# 411618_029_3_6.net
KiCad netlist of a schematic drawn in Altium Designer
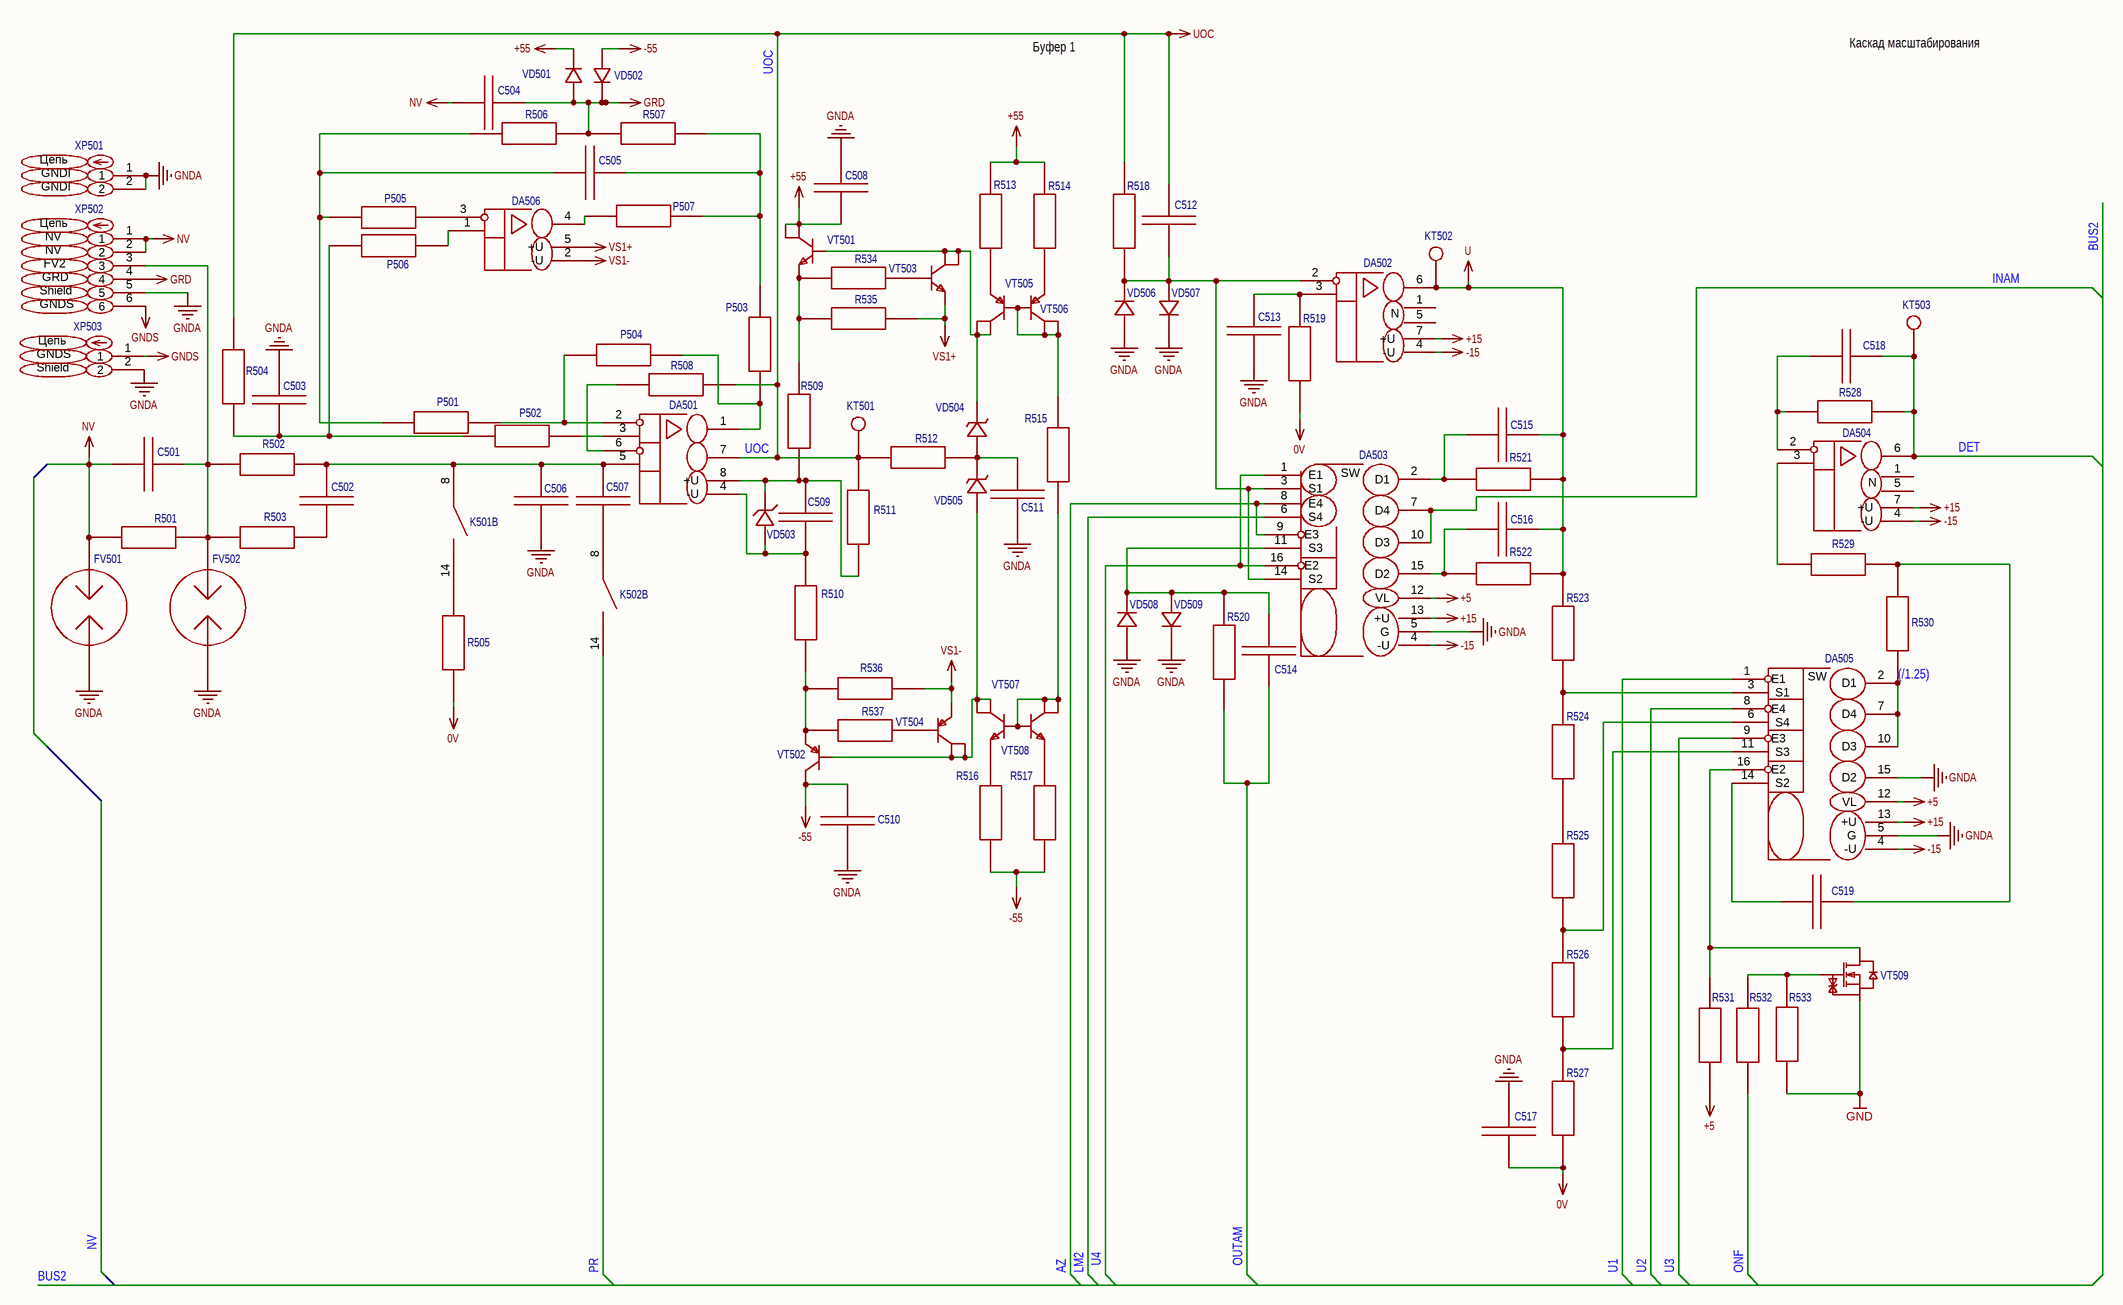
[diagram p0: УШЯИ.411618.029Э Э3 Лист 6.schdoc]

(export (version "E")
  (design (tool "Eeschema 10.0.6"))
  (components
    (comp (ref "C501")
      (value "Конденсатор К10-17Б М47 47пФ  NP0 5% [DIP]")
      (footprint "Конденсатор К10-17Б М47 X.X.xФ  NP0 5% [DIP 8мм]")
      (fields (field (name "MANUFACTURER PART") "К10-17Б М47") (field (name "CONTRIBUTOR") "jordanjin"))
      (libsource (lib "altium-import") (part "root_2_Конденсатор К10-17Б М47 47пФ  NP0 5% [DIP]_"))
    )
    (comp (ref "C502")
      (value "Конденсатор К10-17Б М47 47пФ  NP0 5% [DIP]")
      (footprint "Конденсатор К10-17Б М47 X.X.xФ  NP0 5% [DIP 8мм]")
      (fields (field (name "MANUFACTURER PART") "К10-17Б М47") (field (name "CONTRIBUTOR") "jordanjin"))
      (libsource (lib "altium-import") (part "root_3_Конденсатор К10-17Б М47 47пФ  NP0 5% [DIP]_"))
    )
    (comp (ref "C503")
      (value "Конденсатор SMD 10пФ 100В X7R 10% [0805]")
      (footprint "C0805")
      (fields (field (name "MANUFACTURER PART") "C0805") (field (name "CONTRIBUTOR") "jordanjin"))
      (libsource (lib "altium-import") (part "root_1_Конденсатор SMD 10пФ 100В X7R 10% [0805]_"))
    )
    (comp (ref "C504")
      (value "Конденсатор К10-17Б М47 0,022мкФ  NP0 5% [DIP]")
      (footprint "Конденсатор К10-17Б М47 X.X.xФ  NP0 5% [DIP 5мм]")
      (fields (field (name "MANUFACTURER PART") "К10-17Б М47") (field (name "CONTRIBUTOR") "jordanjin"))
      (libsource (lib "altium-import") (part "root_0_Конденсатор К10-17Б М47 0,022мкФ  NP0 5% [DIP]_"))
    )
    (comp (ref "C505")
      (value "Конденсатор SMD 10пФ 100В X7R 10% [0805]")
      (footprint "C0805")
      (fields (field (name "MANUFACTURER PART") "К10-17Б М47") (field (name "CONTRIBUTOR") "jordanjin"))
      (libsource (lib "altium-import") (part "root_0_Конденсатор К10-17Б М47 10пФ  NP0 5% [DIP]_"))
    )
    (comp (ref "C506")
      (value "Конденсатор К10-17Б М47 33пФ  NP0 5% [DIP]")
      (footprint "Конденсатор К10-17Б М47 X.X.xФ  NP0 5% [DIP 5мм]")
      (fields (field (name "MANUFACTURER PART") "К10-17Б М47") (field (name "CONTRIBUTOR") "jordanjin"))
      (libsource (lib "altium-import") (part "root_3_Конденсатор К10-17Б М47 33пФ  NP0 5% [DIP]_"))
    )
    (comp (ref "C507")
      (value "Конденсатор К10-17Б М47 47пФ  NP0 5% [DIP]")
      (footprint "Конденсатор К10-17Б М47 X.X.xФ  NP0 5% [DIP 5мм]")
      (fields (field (name "MANUFACTURER PART") "К10-17Б М47") (field (name "CONTRIBUTOR") "jordanjin"))
      (libsource (lib "altium-import") (part "root_1_Конденсатор К10-17Б М47 47пФ  NP0 5% [DIP]_"))
    )
    (comp (ref "C508")
      (value "Конденсатор SMD 0,068мкФ 100В X7R 10% [0805]")
      (footprint "C0805")
      (fields (field (name "MANUFACTURER PART") "C0805") (field (name "CONTRIBUTOR") "jordanjin"))
      (libsource (lib "altium-import") (part "root_1_Конденсатор SMD 0,068мкФ 100В X7R 10% [0805]_"))
    )
    (comp (ref "C509")
      (value "Конденсатор SMD 5600пФ 100В X7R 10% [0805]")
      (footprint "C0805")
      (fields (field (name "MANUFACTURER PART") "C0805") (field (name "CONTRIBUTOR") "jordanjin"))
      (libsource (lib "altium-import") (part "root_1_Конденсатор SMD 5600пФ 100В X7R 10% [0805]_"))
    )
    (comp (ref "C510")
      (value "Конденсатор SMD 0,068мкФ 100В X7R 10% [0805]")
      (footprint "C0805")
      (fields (field (name "MANUFACTURER PART") "C0805") (field (name "CONTRIBUTOR") "jordanjin"))
      (libsource (lib "altium-import") (part "root_3_Конденсатор SMD 0,068мкФ 100В X7R 10% [0805]_"))
    )
    (comp (ref "C511")
      (value "Конденсатор SMD 100пФ 100В X7R 10% [0805]")
      (footprint "C0805")
      (fields (field (name "MANUFACTURER PART") "C0805") (field (name "CONTRIBUTOR") "jordanjin"))
      (libsource (lib "altium-import") (part "root_1_Конденсатор SMD 100пФ 100В X7R 10% [0805]_"))
    )
    (comp (ref "C512")
      (value "Конденсатор SMD 10пФ 100В X7R 10% [0805]")
      (footprint "C0805")
      (fields (field (name "MANUFACTURER PART") "C0805") (field (name "CONTRIBUTOR") "jordanjin"))
      (libsource (lib "altium-import") (part "root_1_Конденсатор SMD 10пФ 100В X7R 10% [0805]_"))
    )
    (comp (ref "C513")
      (value "Конденсатор SMD 51пФ 100В X7R 10% [0805]")
      (footprint "C0805")
      (fields (field (name "MANUFACTURER PART") "C0805") (field (name "CONTRIBUTOR") "jordanjin"))
      (libsource (lib "altium-import") (part "root_3_Конденсатор SMD 51пФ 100В X7R 10% [0805]_"))
    )
    (comp (ref "C514")
      (value "Конденсатор SMD 1500пФ 100В X7R 10% [0805]")
      (footprint "C0805")
      (fields (field (name "MANUFACTURER PART") "C0805") (field (name "CONTRIBUTOR") "jordanjin"))
      (libsource (lib "altium-import") (part "root_1_Конденсатор SMD 1500пФ 100В X7R 10% [0805]_"))
    )
    (comp (ref "C515")
      (value "Конденсатор SMD 100пФ 100В X7R 10% [0805]")
      (footprint "C0805")
      (fields (field (name "MANUFACTURER PART") "C0805") (field (name "CONTRIBUTOR") "jordanjin"))
      (libsource (lib "altium-import") (part "root_2_Конденсатор SMD 100пФ 100В X7R 10% [0805]_"))
    )
    (comp (ref "C516")
      (value "Конденсатор SMD 10пФ 100В X7R 10% [0805]")
      (footprint "C0805")
      (fields (field (name "MANUFACTURER PART") "C0805") (field (name "CONTRIBUTOR") "jordanjin"))
      (libsource (lib "altium-import") (part "root_2_Конденсатор SMD 10пФ 100В X7R 10% [0805]_"))
    )
    (comp (ref "C517")
      (value "Конденсатор SMD 240пФ 100В X7R 10% [0805]")
      (footprint "C0805")
      (fields (field (name "MANUFACTURER PART") "C0805") (field (name "CONTRIBUTOR") "jordanjin"))
      (libsource (lib "altium-import") (part "root_3_Конденсатор SMD 240пФ 100В X7R 10% [0805]_"))
    )
    (comp (ref "C518")
      (value "Конденсатор SMD 33пФ 100В X7R 10% [0805]")
      (footprint "C0805")
      (fields (field (name "MANUFACTURER PART") "C0805") (field (name "CONTRIBUTOR") "jordanjin"))
      (libsource (lib "altium-import") (part "root_0_Конденсатор SMD 33пФ 100В X7R 10% [0805]_"))
    )
    (comp (ref "C519")
      (value "Конденсатор SMD 1500пФ 100В X7R 10% [0805]")
      (footprint "C0805")
      (fields (field (name "MANUFACTURER PART") "C0805") (field (name "CONTRIBUTOR") "jordanjin"))
      (libsource (lib "altium-import") (part "root_0_Конденсатор SMD 1500пФ 100В X7R 10% [0805]_"))
    )
    (comp (ref "DA501")
      (value "Операционный усилитель TLV9152IDR [SOIC-8]")
      (footprint "SOIC-8_L4.9-W3.9-P1.27-LS6.0-BL")
      (fields
        (field (name "SUBPART_NO") "1")
        (field (name "MANUFACTURER") "TI")
        (field (name "MANUFACTURER PART") "TLV9152IDR")
        (field (name "CONTRIBUTOR") "jordanjin")
      )
      (libsource (lib "altium-import") (part "root_0_Операционный усилитель TLV9152IDR [SOIC-8]_"))
    )
    (comp (ref "DA502")
      (value "Операционный усилитель ADA4627-1BRZ [SOIC-8]")
      (footprint "SOIC-8_L5.0-W4.0-P1.27-LS6.1-BL")
      (fields
        (field (name "MANUFACTURER") "Analog Devices")
        (field (name "MANUFACTURER PART") "ADA4627-1BRZ")
        (field (name "CONTRIBUTOR") "jordanjin")
      )
      (libsource (lib "altium-import") (part "root_0_Операционный усилитель ADA4627-1BRZ [SOIC-8]_"))
    )
    (comp (ref "DA503")
      (value "Коммутатор аналоговых сигналов ADG433BRZ [SOIC-16]")
      (footprint "SOIC-16_L9.9-W3.9-P1.27-LS6.0-BL")
      (fields
        (field (name "MANUFACTURER") "Analog Devices")
        (field (name "MANUFACTURER PART") "ADG433BRZ-REEL")
        (field (name "CONTRIBUTOR") "jordanjin")
      )
      (libsource (lib "altium-import") (part "root_0_Коммутатор аналоговых сигналов ADG433BRZ [SOIC-16]_"))
    )
    (comp (ref "DA504")
      (value "Операционный усилитель ADA4627-1BRZ [SOIC-8]")
      (footprint "SOIC-8_L5.0-W4.0-P1.27-LS6.1-BL")
      (fields
        (field (name "MANUFACTURER") "Analog Devices")
        (field (name "MANUFACTURER PART") "ADA4627-1BRZ")
        (field (name "CONTRIBUTOR") "jordanjin")
      )
      (libsource (lib "altium-import") (part "root_0_Операционный усилитель ADA4627-1BRZ [SOIC-8]_"))
    )
    (comp (ref "DA505")
      (value "Коммутатор аналоговых сигналов ADG431BRZ [SOIC-16]")
      (footprint "SOIC-16_L9.9-W3.9-P1.27-LS6.0-BL")
      (fields
        (field (name "MANUFACTURER") "Analog Devices")
        (field (name "MANUFACTURER PART") "ADG431BRZ")
        (field (name "CONTRIBUTOR") "jordanjin")
      )
      (libsource (lib "altium-import") (part "root_0_Коммутатор аналоговых сигналов ADG431BRZ [SOIC-16]_"))
    )
    (comp (ref "DA506")
      (value "Операционный усилитель  TLV9151IDCKR [SC-70-5]")
      (footprint "SC-70-5_L2.1-W1.3-P0.65-LS2.2-BR")
      (fields
        (field (name "MANUFACTURER") "TI")
        (field (name "MANUFACTURER PART") "TLV9151IDCKR")
        (field (name "CONTRIBUTOR") "jordanjin")
      )
      (libsource (lib "altium-import") (part "root_0_Операционный усилитель  TLV9151IDCKR [SC-70-5]_"))
    )
    (comp (ref "FV501")
      (value "Разрядник газонаполненный B88069-X8870-B502 (A81-C90X)")
      (fields
        (field (name "MANUFACTURER") "TDK/EPCOS")
        (field (name "MANUFACTURER PART") "B88069-X8870-B502 (A81-C90X)")
        (field (name "CONTRIBUTOR") "jordanjin")
      )
      (libsource (lib "altium-import") (part "root_0_Разрядник газонаполненный B88069-X8870-B502 (A81-C90X)_"))
    )
    (comp (ref "FV502")
      (value "Разрядник газонаполненный B88069-X8870-B502 (A81-C90X)")
      (fields
        (field (name "MANUFACTURER") "TDK/EPCOS")
        (field (name "MANUFACTURER PART") "B88069-X8870-B502 (A81-C90X)")
        (field (name "CONTRIBUTOR") "jordanjin")
      )
      (libsource (lib "altium-import") (part "root_0_Разрядник газонаполненный B88069-X8870-B502 (A81-C90X)_"))
    )
    (comp (ref "K501")
      (value "Реле герконовое DIP05-1A72-13L  [PCB]")
      (footprint "RELAY-TH_STANDEXMEDER_DIP05-1A72-13L")
      (fields
        (field (name "MANUFACTURER") "STANDEXMEDER")
        (field (name "MANUFACTURER PART") "DIP05-1A72-13L")
        (field (name "SUBPART_NO") "2")
        (field (name "CONTRIBUTOR") "jordanjin")
      )
      (libsource (lib "altium-import") (part "root_0_Реле герконовое DIP05-1A72-13L  [PCB]_"))
    )
    (comp (ref "K502")
      (value "Реле герконовое DIP05-1A72-13L  [PCB]")
      (footprint "RELAY-TH_STANDEXMEDER_DIP05-1A72-13L")
      (fields
        (field (name "MANUFACTURER") "STANDEXMEDER")
        (field (name "MANUFACTURER PART") "DIP05-1A72-13L")
        (field (name "SUBPART_NO") "2")
        (field (name "CONTRIBUTOR") "jordanjin")
      )
      (libsource (lib "altium-import") (part "root_0_Реле герконовое DIP05-1A72-13L  [PCB]_"))
    )
    (comp (ref "KT501")
      (value "Control point")
      (fields (field (name "CONTRIBUTOR") "jordanjin"))
      (libsource (lib "altium-import") (part "root_2_Control point_"))
    )
    (comp (ref "KT502")
      (value "Control point")
      (fields (field (name "CONTRIBUTOR") "jordanjin"))
      (libsource (lib "altium-import") (part "root_2_Control point_"))
    )
    (comp (ref "KT503")
      (value "Control point")
      (fields (field (name "CONTRIBUTOR") "jordanjin"))
      (libsource (lib "altium-import") (part "root_2_Control point_"))
    )
    (comp (ref "P501")
      (value "Перемычка")
      (footprint "R0805")
      (fields (field (name "MANUFACTURER PART") "R0805") (field (name "CONTRIBUTOR") "jordanjin"))
      (libsource (lib "altium-import") (part "root_2_Перемычка_"))
    )
    (comp (ref "P502")
      (value "Перемычка")
      (footprint "R0805")
      (fields (field (name "MANUFACTURER PART") "R0805") (field (name "CONTRIBUTOR") "jordanjin"))
      (libsource (lib "altium-import") (part "root_2_Перемычка_"))
    )
    (comp (ref "P503")
      (value "Перемычка")
      (footprint "R0805")
      (fields (field (name "MANUFACTURER PART") "R0805") (field (name "CONTRIBUTOR") "jordanjin"))
      (libsource (lib "altium-import") (part "root_1_Перемычка_"))
    )
    (comp (ref "P504")
      (value "Перемычка")
      (footprint "R0805")
      (fields (field (name "MANUFACTURER PART") "R0805") (field (name "CONTRIBUTOR") "jordanjin"))
      (libsource (lib "altium-import") (part "root_2_Перемычка_"))
    )
    (comp (ref "P505")
      (value "Перемычка")
      (footprint "R0805")
      (fields (field (name "MANUFACTURER PART") "R0805") (field (name "CONTRIBUTOR") "jordanjin"))
      (libsource (lib "altium-import") (part "root_2_Перемычка_"))
    )
    (comp (ref "P506")
      (value "Перемычка")
      (footprint "R0805")
      (fields (field (name "MANUFACTURER PART") "R0805") (field (name "CONTRIBUTOR") "jordanjin"))
      (libsource (lib "altium-import") (part "root_2_Перемычка_"))
    )
    (comp (ref "P507")
      (value "Перемычка")
      (footprint "R0805")
      (fields (field (name "MANUFACTURER PART") "R0805") (field (name "CONTRIBUTOR") "jordanjin"))
      (libsource (lib "altium-import") (part "root_2_Перемычка_"))
    )
    (comp (ref "R501")
      (value "Резистор C2-29В-0,25 1,2кОм ±0,5% [DIP]")
      (fields (field (name "MANUFACTURER PART") "C2-29В-0,25") (field (name "CONTRIBUTOR") "jordanjin"))
      (libsource (lib "altium-import") (part "root_0_Резистор C2-29В-0,25 1,2кОм ±0,5% [DIP]_"))
    )
    (comp (ref "R502")
      (value "Резистор C2-29В-0,25 301кОм ±0,5% [DIP]")
      (fields (field (name "MANUFACTURER PART") "C2-29В-0,25") (field (name "CONTRIBUTOR") "jordanjin"))
      (libsource (lib "altium-import") (part "root_0_Резистор C2-29В-0,25 301кОм ±0,5% [DIP]_"))
    )
    (comp (ref "R503")
      (value "Резистор C2-29В-0,25 5.1кОм ±0,5% [DIP]")
      (fields (field (name "MANUFACTURER PART") "C2-29В-0,25") (field (name "CONTRIBUTOR") "jordanjin"))
      (libsource (lib "altium-import") (part "root_0_Резистор C2-29В-0,25 5.1кОм ±0,5% [DIP]_"))
    )
    (comp (ref "R504")
      (value "Резистор 91кОм 0,125Вт 1% [0805]")
      (footprint "R0805")
      (fields (field (name "MANUFACTURER PART") "R0805") (field (name "CONTRIBUTOR") "jordanjin"))
      (libsource (lib "altium-import") (part "root_1_Резистор 91кОм 0,125Вт 1% [0805]_"))
    )
    (comp (ref "R505")
      (value "Резистор 2.4кОм 0,25Вт 1% [1206]")
      (footprint "R1206")
      (fields (field (name "MANUFACTURER PART") "C2-29В-0,25") (field (name "CONTRIBUTOR") "jordanjin"))
      (libsource (lib "altium-import") (part "root_1_Резистор C2-29В-0,25 2.4кОм ±0,5% [DIP]_"))
    )
    (comp (ref "R506")
      (value "Резистор C2-29В-0,25 51Ом ±0,5% [DIP]")
      (fields (field (name "MANUFACTURER PART") "C2-29В-0,25") (field (name "CONTRIBUTOR") "jordanjin"))
      (libsource (lib "altium-import") (part "root_0_Резистор C2-29В-0,25 51Ом ±0,5% [DIP]_"))
    )
    (comp (ref "R507")
      (value "Резистор C2-29В-0,25 22Ом ±0,5% [DIP]")
      (fields (field (name "MANUFACTURER PART") "C2-29В-0,25") (field (name "CONTRIBUTOR") "jordanjin"))
      (libsource (lib "altium-import") (part "root_0_Резистор C2-29В-0,25 22Ом ±0,5% [DIP]_"))
    )
    (comp (ref "R508")
      (value "Резистор 33Ом 0,125Вт 1% [0805]")
      (footprint "R0805")
      (fields (field (name "MANUFACTURER PART") "R0805") (field (name "CONTRIBUTOR") "jordanjin"))
      (libsource (lib "altium-import") (part "root_0_Резистор 33Ом 0,125Вт 1% [0805]_"))
    )
    (comp (ref "R509")
      (value "Резистор 150Ом 0,125Вт 1% [0805]")
      (footprint "R0805")
      (fields (field (name "MANUFACTURER PART") "R0805") (field (name "CONTRIBUTOR") "jordanjin"))
      (libsource (lib "altium-import") (part "root_1_Резистор 150Ом 0,125Вт 1% [0805]_"))
    )
    (comp (ref "R510")
      (value "Резистор 150Ом 0,125Вт 1% [0805]")
      (footprint "R0805")
      (fields (field (name "MANUFACTURER PART") "R0805") (field (name "CONTRIBUTOR") "jordanjin"))
      (libsource (lib "altium-import") (part "root_1_Резистор 150Ом 0,125Вт 1% [0805]_"))
    )
    (comp (ref "R511")
      (value "Резистор 5,1кОм 0,125Вт 1% [0805]")
      (footprint "R0805")
      (fields (field (name "MANUFACTURER PART") "R0805") (field (name "CONTRIBUTOR") "jordanjin"))
      (libsource (lib "altium-import") (part "root_3_Резистор 5,1кОм 0,125Вт 1% [0805]_"))
    )
    (comp (ref "R512")
      (value "Резистор 4,7кОм 0,125Вт 1% [0805]")
      (footprint "R0805")
      (fields (field (name "MANUFACTURER PART") "R0805") (field (name "CONTRIBUTOR") "jordanjin"))
      (libsource (lib "altium-import") (part "root_0_Резистор 4,7кОм 0,125Вт 1% [0805]_"))
    )
    (comp (ref "R513")
      (value "Резистор 820Ом 0,125Вт 1% [0805]")
      (footprint "R0805")
      (fields (field (name "MANUFACTURER PART") "R0805") (field (name "CONTRIBUTOR") "jordanjin"))
      (libsource (lib "altium-import") (part "root_1_Резистор 820Ом 0,125Вт 1% [0805]_"))
    )
    (comp (ref "R514")
      (value "Резистор 2кОм 0,125Вт 1% [0805]")
      (footprint "R0805")
      (fields (field (name "MANUFACTURER PART") "R0805") (field (name "CONTRIBUTOR") "jordanjin"))
      (libsource (lib "altium-import") (part "root_1_Резистор 2кОм 0,125Вт 1% [0805]_"))
    )
    (comp (ref "R515")
      (value "Резистор 200кОм 0,125Вт 1% [0805]")
      (footprint "R0805")
      (fields (field (name "MANUFACTURER PART") "R0805") (field (name "CONTRIBUTOR") "jordanjin"))
      (libsource (lib "altium-import") (part "root_1_Резистор 200кОм 0,125Вт 1% [0805]_"))
    )
    (comp (ref "R516")
      (value "Резистор 820Ом 0,125Вт 1% [0805]")
      (footprint "R0805")
      (fields (field (name "MANUFACTURER PART") "R0805") (field (name "CONTRIBUTOR") "jordanjin"))
      (libsource (lib "altium-import") (part "root_1_Резистор 820Ом 0,125Вт 1% [0805]_"))
    )
    (comp (ref "R517")
      (value "Резистор 2кОм 0,125Вт 1% [0805]")
      (footprint "R0805")
      (fields (field (name "MANUFACTURER PART") "R0805") (field (name "CONTRIBUTOR") "jordanjin"))
      (libsource (lib "altium-import") (part "root_1_Резистор 2кОм 0,125Вт 1% [0805]_"))
    )
    (comp (ref "R518")
      (value "Резистор 40,2кОм 0.25Вт 1% [1206]")
      (footprint "R0805")
      (fields (field (name "MANUFACTURER PART") "R0805") (field (name "CONTRIBUTOR") "jordanjin"))
      (libsource (lib "altium-import") (part "root_3_Резистор 40,2кОм 0.25Вт 1% [1206]_"))
    )
    (comp (ref "R519")
      (value "Резистор 15кОм 0,125Вт 1% [0805]")
      (footprint "R0805")
      (fields (field (name "MANUFACTURER PART") "R0805") (field (name "CONTRIBUTOR") "jordanjin"))
      (libsource (lib "altium-import") (part "root_1_Резистор 15кОм 0,125Вт 1% [0805]_"))
    )
    (comp (ref "R520")
      (value "Резистор 200кОм 0,125Вт 1% [0805]")
      (footprint "R0805")
      (fields (field (name "MANUFACTURER PART") "R0805") (field (name "CONTRIBUTOR") "jordanjin"))
      (libsource (lib "altium-import") (part "root_3_Резистор 200кОм 0,125Вт 1% [0805]_"))
    )
    (comp (ref "R521")
      (value "Резистор 10кОм 0,125Вт 1% [0805]")
      (footprint "R0805")
      (fields (field (name "MANUFACTURER PART") "R0805") (field (name "CONTRIBUTOR") "jordanjin"))
      (libsource (lib "altium-import") (part "root_0_Резистор 10кОм 0,125Вт 1% [0805]_"))
    )
    (comp (ref "R522")
      (value "Резистор 100кОм 0,125Вт 1% [0805]")
      (footprint "R0805")
      (fields (field (name "MANUFACTURER PART") "R0805") (field (name "CONTRIBUTOR") "jordanjin"))
      (libsource (lib "altium-import") (part "root_0_Резистор 100кОм 0,125Вт 1% [0805]_"))
    )
    (comp (ref "R523")
      (value "Резистор 4,02кОм 0.25Вт 1% [1206]")
      (footprint "R1206")
      (fields (field (name "MANUFACTURER PART") "R1206") (field (name "CONTRIBUTOR") "jordanjin"))
      (libsource (lib "altium-import") (part "root_1_Резистор 4,02кОм 0.25Вт 1% [1206]_"))
    )
    (comp (ref "R524")
      (value "Резистор 4,02кОм 0.25Вт 1% [1206]")
      (footprint "R1206")
      (fields (field (name "MANUFACTURER PART") "R1206") (field (name "CONTRIBUTOR") "jordanjin"))
      (libsource (lib "altium-import") (part "root_1_Резистор 4,02кОм 0.25Вт 1% [1206]_"))
    )
    (comp (ref "R525")
      (value "Резистор 4,02кОм 0.25Вт 1% [1206]")
      (footprint "R1206")
      (fields (field (name "MANUFACTURER PART") "R1206") (field (name "CONTRIBUTOR") "jordanjin"))
      (libsource (lib "altium-import") (part "root_1_Резистор 4,02кОм 0.25Вт 1% [1206]_"))
    )
    (comp (ref "R526")
      (value "Резистор 4,02кОм 0.25Вт 1% [1206]")
      (footprint "R1206")
      (fields (field (name "MANUFACTURER PART") "R1206") (field (name "CONTRIBUTOR") "jordanjin"))
      (libsource (lib "altium-import") (part "root_1_Резистор 4,02кОм 0.25Вт 1% [1206]_"))
    )
    (comp (ref "R527")
      (value "Резистор 4,02кОм 0.25Вт 1% [1206]")
      (footprint "R1206")
      (fields (field (name "MANUFACTURER PART") "R1206") (field (name "CONTRIBUTOR") "jordanjin"))
      (libsource (lib "altium-import") (part "root_1_Резистор 4,02кОм 0.25Вт 1% [1206]_"))
    )
    (comp (ref "R528")
      (value "Резистор 3,6кОм 0,125Вт 1% [0805]")
      (footprint "R0805")
      (fields (field (name "MANUFACTURER PART") "R0805") (field (name "CONTRIBUTOR") "jordanjin"))
      (libsource (lib "altium-import") (part "root_2_Резистор 3,6кОм 0,125Вт 1% [0805]_"))
    )
    (comp (ref "R529")
      (value "Резистор 110кОм 0,125Вт 1% [0805]")
      (footprint "R0805")
      (fields (field (name "MANUFACTURER PART") "R0805") (field (name "CONTRIBUTOR") "jordanjin"))
      (libsource (lib "altium-import") (part "root_2_Резистор 110кОм 0,125Вт 1% [0805]_"))
    )
    (comp (ref "R530")
      (value "Резистор 110кОм 0,125Вт 1% [0805]")
      (footprint "R0805")
      (fields (field (name "MANUFACTURER PART") "R0805") (field (name "CONTRIBUTOR") "jordanjin"))
      (libsource (lib "altium-import") (part "root_1_Резистор 110кОм 0,125Вт 1% [0805]_"))
    )
    (comp (ref "R531")
      (value "Резистор 5,3кОм 0,125Вт 1% [0805]")
      (footprint "R0805")
      (fields (field (name "MANUFACTURER PART") "R0805") (field (name "CONTRIBUTOR") "jordanjin"))
      (libsource (lib "altium-import") (part "root_1_Резистор 5,3кОм 0,125Вт 1% [0805]_"))
    )
    (comp (ref "R532")
      (value "Резистор 100Ом 0,125Вт 1% [0805]")
      (footprint "R0805")
      (fields (field (name "MANUFACTURER PART") "R0805") (field (name "CONTRIBUTOR") "jordanjin"))
      (libsource (lib "altium-import") (part "root_1_Резистор 100Ом 0,125Вт 1% [0805]_"))
    )
    (comp (ref "R533")
      (value "Резистор 100Ом 0,125Вт 1% [0805]")
      (footprint "R0805")
      (fields (field (name "MANUFACTURER PART") "R0805") (field (name "CONTRIBUTOR") "jordanjin"))
      (libsource (lib "altium-import") (part "root_1_Резистор 100Ом 0,125Вт 1% [0805]_"))
    )
    (comp (ref "R534")
      (value "Резистор 400Ом 0,125Вт 1% [0805]")
      (footprint "R0805")
      (fields (field (name "MANUFACTURER PART") "R0805") (field (name "CONTRIBUTOR") "jordanjin"))
      (libsource (lib "altium-import") (part "root_2_Резистор 400Ом 0,125Вт 1% [0805]_"))
    )
    (comp (ref "R535")
      (value "Резистор 150Ом 0,125Вт 1% [0805]")
      (footprint "R0805")
      (fields (field (name "MANUFACTURER PART") "R0805") (field (name "CONTRIBUTOR") "jordanjin"))
      (libsource (lib "altium-import") (part "root_2_Резистор 150Ом 0,125Вт 1% [0805]_"))
    )
    (comp (ref "R536")
      (value "Резистор 150Ом 0,125Вт 1% [0805]")
      (footprint "R0805")
      (fields (field (name "MANUFACTURER PART") "R0805") (field (name "CONTRIBUTOR") "jordanjin"))
      (libsource (lib "altium-import") (part "root_2_Резистор 150Ом 0,125Вт 1% [0805]_"))
    )
    (comp (ref "R537")
      (value "Резистор 400Ом 0,125Вт 1% [0805]")
      (footprint "R0805")
      (fields (field (name "MANUFACTURER PART") "R0805") (field (name "CONTRIBUTOR") "jordanjin"))
      (libsource (lib "altium-import") (part "root_2_Резистор 400Ом 0,125Вт 1% [0805]_"))
    )
    (comp (ref "VD501")
      (value "Диод импульсный 1N4448 [DO-35]")
      (footprint "DO-35_BD2.0-L4.2-P8.20-D0.5-RD")
      (fields
        (field (name "MANUFACTURER") "onsemi")
        (field (name "MANUFACTURER PART") "1N4448TR")
        (field (name "CONTRIBUTOR") "jordanjin")
      )
      (libsource (lib "altium-import") (part "root_3_Диод импульсный 1N4448 [DO-35]_"))
    )
    (comp (ref "VD502")
      (value "Диод импульсный 1N4448 [DO-35]")
      (footprint "DO-35_BD2.0-L4.2-P8.20-D0.5-RD")
      (fields
        (field (name "MANUFACTURER") "onsemi")
        (field (name "MANUFACTURER PART") "1N4448TR")
        (field (name "CONTRIBUTOR") "jordanjin")
      )
      (libsource (lib "altium-import") (part "root_1_Диод импульсный 1N4448 [DO-35]_"))
    )
    (comp (ref "VD503")
      (value "Стабилитрон MMSZ5230B 4.7В 0.5Вт [SOD123]")
      (footprint "SOD-123_L2.8-W1.8-LS3.7-RD")
      (fields (field (name "MANUFACTURER PART") "MMSZ5230B") (field (name "MANUFACTURER") "CJ(江苏长电/长晶)"))
      (libsource (lib "altium-import") (part "root_3_Стабилитрон MMSZ5230B 4.7В 0.5Вт [SOD123]_"))
    )
    (comp (ref "VD504")
      (value "Стабилитрон MMSZ5232B 5.6В 0.5Вт [SOD123]")
      (footprint "SOD-123_L2.7-W1.6-LS3.7-RD")
      (fields
        (field (name "MANUFACTURER") "MCC(美微科)")
        (field (name "MANUFACTURER PART") "MMSZ5232B-TP")
        (field (name "CONTRIBUTOR") "LCSC")
      )
      (libsource (lib "altium-import") (part "root_3_Стабилитрон MMSZ5232B 5.6В 0.5Вт [SOD123]_"))
    )
    (comp (ref "VD505")
      (value "Стабилитрон MMSZ5232B 5.6В 0.5Вт [SOD123]")
      (footprint "SOD-123_L2.7-W1.6-LS3.7-RD")
      (fields
        (field (name "MANUFACTURER") "MCC(美微科)")
        (field (name "MANUFACTURER PART") "MMSZ5232B-TP")
        (field (name "CONTRIBUTOR") "LCSC")
      )
      (libsource (lib "altium-import") (part "root_3_Стабилитрон MMSZ5232B 5.6В 0.5Вт [SOD123]_"))
    )
    (comp (ref "VD506")
      (value "Диод импульсный 1N4448 [SOD-123]")
      (footprint "SOD-123_L2.7-W1.6-LS3.7-RD-1")
      (fields
        (field (name "MANUFACTURER") "YANGJIE")
        (field (name "MANUFACTURER PART") "1N4448WQ")
        (field (name "CONTRIBUTOR") "jordanjin")
      )
      (libsource (lib "altium-import") (part "root_3_Диод импульсный 1N4448 [SOD-123]_"))
    )
    (comp (ref "VD507")
      (value "Диод импульсный 1N4448 [SOD-123]")
      (footprint "SOD-123_L2.7-W1.6-LS3.7-RD-1")
      (fields
        (field (name "MANUFACTURER") "YANGJIE")
        (field (name "MANUFACTURER PART") "1N4448WQ")
        (field (name "CONTRIBUTOR") "jordanjin")
      )
      (libsource (lib "altium-import") (part "root_1_Диод импульсный 1N4448 [SOD-123]_"))
    )
    (comp (ref "VD508")
      (value "Диод импульсный 1N4448 [SOD-123]")
      (footprint "SOD-123_L2.7-W1.6-LS3.7-RD-1")
      (fields
        (field (name "MANUFACTURER") "YANGJIE")
        (field (name "MANUFACTURER PART") "1N4448WQ")
        (field (name "CONTRIBUTOR") "jordanjin")
      )
      (libsource (lib "altium-import") (part "root_3_Диод импульсный 1N4448 [SOD-123]_"))
    )
    (comp (ref "VD509")
      (value "Диод импульсный 1N4448 [SOD-123]")
      (footprint "SOD-123_L2.7-W1.6-LS3.7-RD-1")
      (fields
        (field (name "MANUFACTURER") "YANGJIE")
        (field (name "MANUFACTURER PART") "1N4448WQ")
        (field (name "CONTRIBUTOR") "jordanjin")
      )
      (libsource (lib "altium-import") (part "root_1_Диод импульсный 1N4448 [SOD-123]_"))
    )
    (comp (ref "VT501")
      (value "Транзистор DZT658 NPN [SOT223]")
      (footprint "SOT-223-3_L6.5-W3.4-P2.30-LS7.0-BR")
      (fields
        (field (name "MANUFACTURER") "DIODES(美台)")
        (field (name "MANUFACTURER PART") "DZT658-13")
        (field (name "CONTRIBUTOR") "LCSC")
      )
      (libsource (lib "altium-import") (part "root_0_Транзистор DZT658 NPN [SOT223]_"))
    )
    (comp (ref "VT502")
      (value "Транзистор FZT758 PNP [SOT223]")
      (footprint "SOT-223_L6.5-W3.5-P2.30-LS7.0-BR")
      (fields
        (field (name "MANUFACTURER") "DIODES(美台)")
        (field (name "MANUFACTURER PART") "FZT758TA")
        (field (name "CONTRIBUTOR") "LCSC")
      )
      (libsource (lib "altium-import") (part "root_0_Транзистор FZT758 PNP [SOT223]_"))
    )
    (comp (ref "VT503")
      (value "Транзистор DZTA42 NPN [SOT223]")
      (footprint "SOT-223-4_L6.5-W3.5-P2.30-LS7.0-BR")
      (fields
        (field (name "MANUFACTURER") "DIODES(美台)")
        (field (name "MANUFACTURER PART") "DZTA42-13")
        (field (name "CONTRIBUTOR") "LCSC")
      )
      (libsource (lib "altium-import") (part "root_0_Транзистор DZTA42 NPN [SOT223]_"))
    )
    (comp (ref "VT504")
      (value "Транзистор DZTA92 PNP [SOT223]")
      (footprint "SOT-223-3_L6.5-W3.4-P2.30-LS7.0-BR")
      (fields
        (field (name "MANUFACTURER") "DIODES(美台)")
        (field (name "MANUFACTURER PART") "DZTA92-13")
        (field (name "CONTRIBUTOR") "lcsc")
      )
      (libsource (lib "altium-import") (part "root_0_Транзистор DZTA92 PNP [SOT223]_"))
    )
    (comp (ref "VT505")
      (value "Транзистор DZTA92 PNP [SOT223]")
      (footprint "SOT-223-3_L6.5-W3.4-P2.30-LS7.0-BR")
      (fields
        (field (name "MANUFACTURER") "DIODES(美台)")
        (field (name "MANUFACTURER PART") "DZTA92-13")
        (field (name "CONTRIBUTOR") "lcsc")
      )
      (libsource (lib "") (part "root_0_Транзистор DZTA92 PNP [SOT223]__1"))
    )
    (comp (ref "VT506")
      (value "Транзистор DZTA92 PNP [SOT223]")
      (footprint "SOT-223-3_L6.5-W3.4-P2.30-LS7.0-BR")
      (fields
        (field (name "MANUFACTURER") "DIODES(美台)")
        (field (name "MANUFACTURER PART") "DZTA92-13")
        (field (name "CONTRIBUTOR") "lcsc")
      )
      (libsource (lib "altium-import") (part "root_0_Транзистор DZTA92 PNP [SOT223]_"))
    )
    (comp (ref "VT507")
      (value "Транзистор DZTA42 NPN [SOT223]")
      (footprint "SOT-223-4_L6.5-W3.5-P2.30-LS7.0-BR")
      (fields
        (field (name "MANUFACTURER") "DIODES(美台)")
        (field (name "MANUFACTURER PART") "DZTA42-13")
        (field (name "CONTRIBUTOR") "LCSC")
      )
      (libsource (lib "") (part "root_0_Транзистор DZTA42 NPN [SOT223]__1"))
    )
    (comp (ref "VT508")
      (value "Транзистор DZTA42 NPN [SOT223]")
      (footprint "SOT-223-4_L6.5-W3.5-P2.30-LS7.0-BR")
      (fields
        (field (name "MANUFACTURER") "DIODES(美台)")
        (field (name "MANUFACTURER PART") "DZTA42-13")
        (field (name "CONTRIBUTOR") "LCSC")
      )
      (libsource (lib "altium-import") (part "root_0_Транзистор DZTA42 NPN [SOT223]_"))
    )
    (comp (ref "VT509")
      (value "Транзистор полевой MOSFET N-канальный BSS138BK [SOT-23-3]")
      (footprint "SOT-23-3_L2.9-W1.3-P1.90-LS2.4-BR")
      (fields
        (field (name "MANUFACTURER") "ElecSuper(静芯)")
        (field (name "MANUFACTURER PART") "BSS138BK")
        (field (name "CONTRIBUTOR") "lcsc")
      )
      (libsource (lib "altium-import") (part "root_0_Транзистор полевой MOSFET N-канальный BSS138BK [SOT-23-3]_"))
    )
    (comp (ref "XP501")
      (value "Вилка на плату 280370-2 шаг 2.54мм")
      (footprint "CONN-TH_280370-2")
      (fields
        (field (name "MANUFACTURER") "TE Connectivity")
        (field (name "MANUFACTURER PART") "280370-2")
        (field (name "CONTRIBUTOR") "jordanjin")
      )
      (libsource (lib "altium-import") (part "root_0_Вилка на плату 280370-2 шаг 2.54мм_"))
    )
    (comp (ref "XP502")
      (value "Вилка на плату 280372-1 шаг 2.54мм")
      (footprint "CONN-TH_280372-1")
      (fields
        (field (name "MANUFACTURER") "TE Connectivity")
        (field (name "MANUFACTURER PART") "280372-1")
        (field (name "CONTRIBUTOR") "jordanjin")
      )
      (libsource (lib "altium-import") (part "root_0_Вилка на плату 280372-1 шаг 2.54мм_"))
    )
    (comp (ref "XP503")
      (value "Вилка на плату 280370-2 шаг 2.54мм")
      (footprint "CONN-TH_280370-2")
      (fields
        (field (name "MANUFACTURER") "TE Connectivity")
        (field (name "MANUFACTURER PART") "280370-2")
        (field (name "CONTRIBUTOR") "jordanjin")
      )
      (libsource (lib "altium-import") (part "root_0_Вилка на плату 280370-2 шаг 2.54мм_"))
    )
  )
  (nets
    (net (code "2") (name "+5") (class "Default")
      (node (ref "DA503") (pin "12") (pinfunction "VL_12") (pintype "passive"))
      (node (ref "DA505") (pin "12") (pinfunction "VL_12") (pintype "passive"))
      (node (ref "R531") (pin "1") (pinfunction "1_1") (pintype "passive"))
    )
    (net (code "3") (name "+15") (class "Default")
      (node (ref "DA502") (pin "7") (pinfunction "+U_7") (pintype "passive"))
      (node (ref "DA503") (pin "13") (pinfunction "+U_13") (pintype "passive"))
      (node (ref "DA504") (pin "7") (pinfunction "+U_7") (pintype "passive"))
      (node (ref "DA505") (pin "13") (pinfunction "+U_13") (pintype "passive"))
    )
    (net (code "4") (name "+55") (class "Default")
      (node (ref "C508") (pin "1") (pinfunction "1_1") (pintype "passive"))
      (node (ref "R513") (pin "2") (pinfunction "2_2") (pintype "passive"))
      (node (ref "R514") (pin "2") (pinfunction "2_2") (pintype "passive"))
      (node (ref "VD501") (pin "1") (pinfunction "1_1") (pintype "passive"))
      (node (ref "VT501") (pin "2") (pinfunction "C_2") (pintype "passive"))
      (node (ref "VT501") (pin "4") (pinfunction "C_4") (pintype "passive"))
    )
    (net (code "5") (name "-15") (class "Default")
      (node (ref "DA502") (pin "4") (pinfunction "-U_4") (pintype "passive"))
      (node (ref "DA503") (pin "4") (pinfunction "-U_4") (pintype "passive"))
      (node (ref "DA504") (pin "4") (pinfunction "-U_4") (pintype "passive"))
      (node (ref "DA505") (pin "4") (pinfunction "-U_4") (pintype "passive"))
    )
    (net (code "6") (name "-55") (class "Default")
      (node (ref "C510") (pin "1") (pinfunction "1_1") (pintype "passive"))
      (node (ref "R516") (pin "1") (pinfunction "1_1") (pintype "passive"))
      (node (ref "R517") (pin "1") (pinfunction "1_1") (pintype "passive"))
      (node (ref "VD502") (pin "2") (pinfunction "2_2") (pintype "passive"))
      (node (ref "VT502") (pin "2") (pinfunction "C_2") (pintype "passive"))
      (node (ref "VT502") (pin "4") (pinfunction "C_4") (pintype "passive"))
    )
    (net (code "7") (name "/({slash}1.25)") (class "Default")
      (node (ref "DA505") (pin "10") (pinfunction "D3_10") (pintype "passive"))
      (node (ref "DA505") (pin "2") (pinfunction "D1_2") (pintype "passive"))
      (node (ref "DA505") (pin "7") (pinfunction "D4_7") (pintype "passive"))
      (node (ref "R530") (pin "1") (pinfunction "1_1") (pintype "passive"))
    )
    (net (code "8") (name "/AZ") (class "Default")
      (node (ref "DA503") (pin "8") (pinfunction "E4_8") (pintype "passive"))
      (node (ref "DA503") (pin "9") (pinfunction "E3_9") (pintype "passive"))
    )
    (net (code "9") (name "/DET") (class "Default")
      (node (ref "C518") (pin "2") (pinfunction "2_2") (pintype "passive"))
      (node (ref "DA504") (pin "6") (pinfunction "OUT_6") (pintype "passive"))
      (node (ref "KT503") (pin "1") (pinfunction "1_1") (pintype "passive"))
      (node (ref "R528") (pin "1") (pinfunction "1_1") (pintype "passive"))
    )
    (net (code "10") (name "/INAM") (class "Default")
      (node (ref "DA503") (pin "10") (pinfunction "D3_10") (pintype "passive"))
      (node (ref "DA503") (pin "7") (pinfunction "D4_7") (pintype "passive"))
    )
    (net (code "11") (name "/LM2") (class "Default")
      (node (ref "DA503") (pin "6") (pinfunction "S4_6") (pintype "passive"))
    )
    (net (code "12") (name "/ONF") (class "Default")
      (node (ref "R532") (pin "1") (pinfunction "1_1") (pintype "passive"))
    )
    (net (code "13") (name "/OUTAM") (class "Default")
      (node (ref "C514") (pin "1") (pinfunction "1_1") (pintype "passive"))
      (node (ref "R520") (pin "2") (pinfunction "2_2") (pintype "passive"))
    )
    (net (code "14") (name "/PR") (class "Default")
      (node (ref "K502") (pin "14") (pinfunction "14_14") (pintype "passive"))
    )
    (net (code "15") (name "/U1") (class "Default")
      (node (ref "DA505") (pin "1") (pinfunction "E1_1") (pintype "passive"))
    )
    (net (code "16") (name "/U2") (class "Default")
      (node (ref "DA505") (pin "8") (pinfunction "E4_8") (pintype "passive"))
    )
    (net (code "17") (name "/U3") (class "Default")
      (node (ref "DA505") (pin "9") (pinfunction "E3_9") (pintype "passive"))
    )
    (net (code "18") (name "/U4") (class "Default")
      (node (ref "DA503") (pin "1") (pinfunction "E1_1") (pintype "passive"))
      (node (ref "DA503") (pin "16") (pinfunction "E2_16") (pintype "passive"))
    )
    (net (code "20") (name "0V") (class "Default")
      (node (ref "C517") (pin "2") (pinfunction "2_2") (pintype "passive"))
      (node (ref "R505") (pin "1") (pinfunction "1_1") (pintype "passive"))
      (node (ref "R519") (pin "1") (pinfunction "1_1") (pintype "passive"))
      (node (ref "R527") (pin "1") (pinfunction "1_1") (pintype "passive"))
    )
    (net (code "21") (name "GND") (class "Default")
      (node (ref "R533") (pin "1") (pinfunction "1_1") (pintype "passive"))
      (node (ref "VT509") (pin "2") (pinfunction "S_2") (pintype "passive"))
    )
    (net (code "22") (name "GNDA") (class "Default")
      (node (ref "C503") (pin "2") (pinfunction "2_2") (pintype "passive"))
      (node (ref "C506") (pin "2") (pinfunction "2_2") (pintype "passive"))
      (node (ref "C508") (pin "2") (pinfunction "2_2") (pintype "passive"))
      (node (ref "C510") (pin "2") (pinfunction "2_2") (pintype "passive"))
      (node (ref "C511") (pin "1") (pinfunction "1_1") (pintype "passive"))
      (node (ref "C513") (pin "2") (pinfunction "2_2") (pintype "passive"))
      (node (ref "C517") (pin "1") (pinfunction "1_1") (pintype "passive"))
      (node (ref "DA503") (pin "5") (pinfunction "G_5") (pintype "passive"))
      (node (ref "DA505") (pin "15") (pinfunction "D2_15") (pintype "passive"))
      (node (ref "DA505") (pin "5") (pinfunction "G_5") (pintype "passive"))
      (node (ref "FV501") (pin "2") (pinfunction "2_2") (pintype "passive"))
      (node (ref "FV502") (pin "2") (pinfunction "2_2") (pintype "passive"))
      (node (ref "VD506") (pin "2") (pinfunction "A_2") (pintype "passive"))
      (node (ref "VD507") (pin "1") (pinfunction "C_1") (pintype "passive"))
      (node (ref "VD508") (pin "2") (pinfunction "A_2") (pintype "passive"))
      (node (ref "VD509") (pin "1") (pinfunction "C_1") (pintype "passive"))
      (node (ref "XP501") (pin "1") (pinfunction "1_1") (pintype "passive"))
      (node (ref "XP501") (pin "2") (pinfunction "2_2") (pintype "passive"))
      (node (ref "XP502") (pin "5") (pinfunction "5_5") (pintype "passive"))
      (node (ref "XP503") (pin "2") (pinfunction "2_2") (pintype "passive"))
    )
    (net (code "23") (name "GNDS") (class "Default")
      (node (ref "XP502") (pin "6") (pinfunction "6_6") (pintype "passive"))
      (node (ref "XP503") (pin "1") (pinfunction "1_1") (pintype "passive"))
    )
    (net (code "24") (name "GRD") (class "Default")
      (node (ref "C504") (pin "2") (pinfunction "2_2") (pintype "passive"))
      (node (ref "R506") (pin "2") (pinfunction "2_2") (pintype "passive"))
      (node (ref "R507") (pin "1") (pinfunction "1_1") (pintype "passive"))
      (node (ref "VD501") (pin "2") (pinfunction "2_2") (pintype "passive"))
      (node (ref "VD502") (pin "1") (pinfunction "1_1") (pintype "passive"))
      (node (ref "XP502") (pin "4") (pinfunction "4_4") (pintype "passive"))
    )
    (net (code "25") (name "NV") (class "Default")
      (node (ref "C501") (pin "2") (pinfunction "2_2") (pintype "passive"))
      (node (ref "C504") (pin "1") (pinfunction "1_1") (pintype "passive"))
      (node (ref "FV501") (pin "1") (pinfunction "1_1") (pintype "passive"))
      (node (ref "R501") (pin "1") (pinfunction "1_1") (pintype "passive"))
      (node (ref "XP502") (pin "1") (pinfunction "1_1") (pintype "passive"))
      (node (ref "XP502") (pin "2") (pinfunction "2_2") (pintype "passive"))
    )
    (net (code "26") (name "Net-(C501-Pad1)") (class "Default")
      (node (ref "C501") (pin "1") (pinfunction "1_1") (pintype "passive"))
      (node (ref "FV502") (pin "1") (pinfunction "1_1") (pintype "passive"))
      (node (ref "R501") (pin "2") (pinfunction "2_2") (pintype "passive"))
      (node (ref "R502") (pin "1") (pinfunction "1_1") (pintype "passive"))
      (node (ref "R503") (pin "1") (pinfunction "1_1") (pintype "passive"))
      (node (ref "XP502") (pin "3") (pinfunction "3_3") (pintype "passive"))
    )
    (net (code "27") (name "Net-(C502-Pad1)") (class "Default")
      (node (ref "C502") (pin "1") (pinfunction "1_1") (pintype "passive"))
      (node (ref "C506") (pin "1") (pinfunction "1_1") (pintype "passive"))
      (node (ref "C507") (pin "2") (pinfunction "2_2") (pintype "passive"))
      (node (ref "DA501") (pin "5") (pinfunction "+IN_5") (pintype "passive"))
      (node (ref "K501") (pin "8") (pinfunction "8_8") (pintype "passive"))
      (node (ref "R502") (pin "2") (pinfunction "2_2") (pintype "passive"))
    )
    (net (code "28") (name "Net-(C502-Pad2)") (class "Default")
      (node (ref "C502") (pin "2") (pinfunction "2_2") (pintype "passive"))
      (node (ref "R503") (pin "2") (pinfunction "2_2") (pintype "passive"))
    )
    (net (code "29") (name "Net-(C503-Pad1)") (class "Default")
      (node (ref "C503") (pin "1") (pinfunction "1_1") (pintype "passive"))
      (node (ref "P502") (pin "2") (pinfunction "2_2") (pintype "passive"))
      (node (ref "P506") (pin "2") (pinfunction "2_2") (pintype "passive"))
      (node (ref "R504") (pin "1") (pinfunction "1_1") (pintype "passive"))
    )
    (net (code "30") (name "Net-(C505-Pad1)") (class "Default")
      (node (ref "C505") (pin "1") (pinfunction "1_1") (pintype "passive"))
      (node (ref "P501") (pin "2") (pinfunction "2_2") (pintype "passive"))
      (node (ref "P505") (pin "2") (pinfunction "2_2") (pintype "passive"))
      (node (ref "R506") (pin "1") (pinfunction "1_1") (pintype "passive"))
    )
    (net (code "31") (name "Net-(C505-Pad2)") (class "Default")
      (node (ref "C505") (pin "2") (pinfunction "2_2") (pintype "passive"))
      (node (ref "P503") (pin "2") (pinfunction "2_2") (pintype "passive"))
      (node (ref "P507") (pin "1") (pinfunction "1_1") (pintype "passive"))
      (node (ref "R507") (pin "2") (pinfunction "2_2") (pintype "passive"))
    )
    (net (code "32") (name "Net-(C507-Pad1)") (class "Default")
      (node (ref "C507") (pin "1") (pinfunction "1_1") (pintype "passive"))
      (node (ref "K502") (pin "8") (pinfunction "8_8") (pintype "passive"))
    )
    (net (code "33") (name "Net-(C519-Pad2)") (class "Default")
      (node (ref "C519") (pin "2") (pinfunction "2_2") (pintype "passive"))
      (node (ref "R529") (pin "1") (pinfunction "1_1") (pintype "passive"))
      (node (ref "R530") (pin "2") (pinfunction "2_2") (pintype "passive"))
    )
    (net (code "34") (name "Net-(DA501-+IN-Pad3)") (class "Default")
      (node (ref "DA501") (pin "3") (pinfunction "+IN_3") (pintype "passive"))
      (node (ref "P502") (pin "1") (pinfunction "1_1") (pintype "passive"))
    )
    (net (code "35") (name "Net-(DA501-+U)") (class "Default")
      (node (ref "C509") (pin "2") (pinfunction "2_2") (pintype "passive"))
      (node (ref "DA501") (pin "8") (pinfunction "+U_8") (pintype "passive"))
      (node (ref "R509") (pin "1") (pinfunction "1_1") (pintype "passive"))
      (node (ref "R511") (pin "2") (pinfunction "2_2") (pintype "passive"))
      (node (ref "VD503") (pin "1") (pinfunction "K_1") (pintype "passive"))
    )
    (net (code "36") (name "Net-(DA501--IN-Pad2)") (class "Default")
      (node (ref "DA501") (pin "2") (pinfunction "-IN_2") (pintype "passive"))
      (node (ref "P501") (pin "1") (pinfunction "1_1") (pintype "passive"))
      (node (ref "P504") (pin "2") (pinfunction "2_2") (pintype "passive"))
    )
    (net (code "37") (name "Net-(DA501--IN-Pad6)") (class "Default")
      (node (ref "DA501") (pin "6") (pinfunction "-IN_6") (pintype "passive"))
      (node (ref "R508") (pin "1") (pinfunction "1_1") (pintype "passive"))
    )
    (net (code "38") (name "Net-(DA501--U)") (class "Default")
      (node (ref "C509") (pin "1") (pinfunction "1_1") (pintype "passive"))
      (node (ref "DA501") (pin "4") (pinfunction "-U_4") (pintype "passive"))
      (node (ref "R510") (pin "2") (pinfunction "2_2") (pintype "passive"))
      (node (ref "VD503") (pin "2") (pinfunction "A_2") (pintype "passive"))
    )
    (net (code "39") (name "Net-(DA501-OUT-Pad1)") (class "Default")
      (node (ref "DA501") (pin "1") (pinfunction "OUT_1") (pintype "passive"))
      (node (ref "P503") (pin "1") (pinfunction "1_1") (pintype "passive"))
      (node (ref "P504") (pin "1") (pinfunction "1_1") (pintype "passive"))
    )
    (net (code "40") (name "Net-(DA502-+IN)") (class "Default")
      (node (ref "C513") (pin "1") (pinfunction "1_1") (pintype "passive"))
      (node (ref "DA502") (pin "3") (pinfunction "+IN_3") (pintype "passive"))
      (node (ref "R519") (pin "2") (pinfunction "2_2") (pintype "passive"))
    )
    (net (code "41") (name "Net-(DA502--IN)") (class "Default")
      (node (ref "C512") (pin "1") (pinfunction "1_1") (pintype "passive"))
      (node (ref "DA502") (pin "2") (pinfunction "-IN_2") (pintype "passive"))
      (node (ref "DA503") (pin "14") (pinfunction "S2_14") (pintype "passive"))
      (node (ref "DA503") (pin "3") (pinfunction "S1_3") (pintype "passive"))
      (node (ref "R518") (pin "2") (pinfunction "2_2") (pintype "passive"))
      (node (ref "VD506") (pin "1") (pinfunction "C_1") (pintype "passive"))
      (node (ref "VD507") (pin "2") (pinfunction "A_2") (pintype "passive"))
    )
    (net (code "42") (name "Net-(DA503-D1)") (class "Default")
      (node (ref "C515") (pin "2") (pinfunction "2_2") (pintype "passive"))
      (node (ref "DA503") (pin "2") (pinfunction "D1_2") (pintype "passive"))
      (node (ref "R521") (pin "1") (pinfunction "1_1") (pintype "passive"))
    )
    (net (code "43") (name "Net-(DA503-D2)") (class "Default")
      (node (ref "C516") (pin "2") (pinfunction "2_2") (pintype "passive"))
      (node (ref "DA503") (pin "15") (pinfunction "D2_15") (pintype "passive"))
      (node (ref "R522") (pin "1") (pinfunction "1_1") (pintype "passive"))
    )
    (net (code "44") (name "Net-(DA503-S3)") (class "Default")
      (node (ref "C514") (pin "2") (pinfunction "2_2") (pintype "passive"))
      (node (ref "DA503") (pin "11") (pinfunction "S3_11") (pintype "passive"))
      (node (ref "R520") (pin "1") (pinfunction "1_1") (pintype "passive"))
      (node (ref "VD508") (pin "1") (pinfunction "C_1") (pintype "passive"))
      (node (ref "VD509") (pin "2") (pinfunction "A_2") (pintype "passive"))
    )
    (net (code "45") (name "Net-(DA504-+IN)") (class "Default")
      (node (ref "DA504") (pin "3") (pinfunction "+IN_3") (pintype "passive"))
      (node (ref "R529") (pin "2") (pinfunction "2_2") (pintype "passive"))
    )
    (net (code "46") (name "Net-(DA504--IN)") (class "Default")
      (node (ref "C518") (pin "1") (pinfunction "1_1") (pintype "passive"))
      (node (ref "DA504") (pin "2") (pinfunction "-IN_2") (pintype "passive"))
      (node (ref "R528") (pin "2") (pinfunction "2_2") (pintype "passive"))
    )
    (net (code "47") (name "Net-(DA505-E2)") (class "Default")
      (node (ref "DA505") (pin "16") (pinfunction "E2_16") (pintype "passive"))
      (node (ref "R531") (pin "2") (pinfunction "2_2") (pintype "passive"))
      (node (ref "VT509") (pin "3") (pinfunction "D_3") (pintype "passive"))
    )
    (net (code "48") (name "Net-(DA505-S1)") (class "Default")
      (node (ref "DA505") (pin "3") (pinfunction "S1_3") (pintype "passive"))
      (node (ref "R523") (pin "1") (pinfunction "1_1") (pintype "passive"))
      (node (ref "R524") (pin "2") (pinfunction "2_2") (pintype "passive"))
    )
    (net (code "49") (name "Net-(DA505-S2)") (class "Default")
      (node (ref "C519") (pin "1") (pinfunction "1_1") (pintype "passive"))
      (node (ref "DA505") (pin "14") (pinfunction "S2_14") (pintype "passive"))
    )
    (net (code "50") (name "Net-(DA505-S3)") (class "Default")
      (node (ref "DA505") (pin "11") (pinfunction "S3_11") (pintype "passive"))
      (node (ref "R526") (pin "1") (pinfunction "1_1") (pintype "passive"))
      (node (ref "R527") (pin "2") (pinfunction "2_2") (pintype "passive"))
    )
    (net (code "51") (name "Net-(DA505-S4)") (class "Default")
      (node (ref "DA505") (pin "6") (pinfunction "S4_6") (pintype "passive"))
      (node (ref "R525") (pin "1") (pinfunction "1_1") (pintype "passive"))
      (node (ref "R526") (pin "2") (pinfunction "2_2") (pintype "passive"))
    )
    (net (code "52") (name "Net-(DA506-+IN)") (class "Default")
      (node (ref "DA506") (pin "1") (pinfunction "+IN_1") (pintype "passive"))
      (node (ref "P506") (pin "1") (pinfunction "1_1") (pintype "passive"))
    )
    (net (code "53") (name "Net-(DA506--IN)") (class "Default")
      (node (ref "DA506") (pin "3") (pinfunction "-IN_3") (pintype "passive"))
      (node (ref "P505") (pin "1") (pinfunction "1_1") (pintype "passive"))
    )
    (net (code "54") (name "Net-(DA506-OUT)") (class "Default")
      (node (ref "DA506") (pin "4") (pinfunction "OUT_4") (pintype "passive"))
      (node (ref "P507") (pin "2") (pinfunction "2_2") (pintype "passive"))
    )
    (net (code "55") (name "Net-(K501-Pad14)") (class "Default")
      (node (ref "K501") (pin "14") (pinfunction "14_14") (pintype "passive"))
      (node (ref "R505") (pin "2") (pinfunction "2_2") (pintype "passive"))
    )
    (net (code "56") (name "Net-(R524-Pad1)") (class "Default")
      (node (ref "R524") (pin "1") (pinfunction "1_1") (pintype "passive"))
      (node (ref "R525") (pin "2") (pinfunction "2_2") (pintype "passive"))
    )
    (net (code "57") (name "Net-(VD504-A)") (class "Default")
      (node (ref "C511") (pin "2") (pinfunction "2_2") (pintype "passive"))
      (node (ref "R512") (pin "2") (pinfunction "2_2") (pintype "passive"))
      (node (ref "VD504") (pin "2") (pinfunction "A_2") (pintype "passive"))
      (node (ref "VD505") (pin "1") (pinfunction "K_1") (pintype "passive"))
    )
    (net (code "58") (name "Net-(VD504-K)") (class "Default")
      (node (ref "VD504") (pin "1") (pinfunction "K_1") (pintype "passive"))
      (node (ref "VT501") (pin "1") (pinfunction "B_1") (pintype "passive"))
      (node (ref "VT503") (pin "2") (pinfunction "C_2") (pintype "passive"))
      (node (ref "VT503") (pin "4") (pinfunction "C_4") (pintype "passive"))
      (node (ref "VT505") (pin "2") (pinfunction "C_2") (pintype "passive"))
      (node (ref "VT505") (pin "4") (pinfunction "C_4") (pintype "passive"))
    )
    (net (code "59") (name "Net-(VD505-A)") (class "Default")
      (node (ref "VD505") (pin "2") (pinfunction "A_2") (pintype "passive"))
      (node (ref "VT502") (pin "1") (pinfunction "B_1") (pintype "passive"))
      (node (ref "VT504") (pin "2") (pinfunction "C_2") (pintype "passive"))
      (node (ref "VT504") (pin "4") (pinfunction "C_4") (pintype "passive"))
      (node (ref "VT507") (pin "2") (pinfunction "C_2") (pintype "passive"))
      (node (ref "VT507") (pin "4") (pinfunction "C_4") (pintype "passive"))
    )
    (net (code "60") (name "Net-(VT501-E)") (class "Default")
      (node (ref "R509") (pin "2") (pinfunction "2_2") (pintype "passive"))
      (node (ref "R534") (pin "2") (pinfunction "2_2") (pintype "passive"))
      (node (ref "R535") (pin "2") (pinfunction "2_2") (pintype "passive"))
      (node (ref "VT501") (pin "3") (pinfunction "E_3") (pintype "passive"))
    )
    (net (code "61") (name "Net-(VT502-E)") (class "Default")
      (node (ref "R510") (pin "1") (pinfunction "1_1") (pintype "passive"))
      (node (ref "R536") (pin "2") (pinfunction "2_2") (pintype "passive"))
      (node (ref "R537") (pin "2") (pinfunction "2_2") (pintype "passive"))
      (node (ref "VT502") (pin "3") (pinfunction "E_3") (pintype "passive"))
    )
    (net (code "62") (name "Net-(VT503-B)") (class "Default")
      (node (ref "R534") (pin "1") (pinfunction "1_1") (pintype "passive"))
      (node (ref "VT503") (pin "1") (pinfunction "B_1") (pintype "passive"))
    )
    (net (code "63") (name "Net-(VT504-B)") (class "Default")
      (node (ref "R537") (pin "1") (pinfunction "1_1") (pintype "passive"))
      (node (ref "VT504") (pin "1") (pinfunction "B_1") (pintype "passive"))
    )
    (net (code "64") (name "Net-(VT505-B)") (class "Default")
      (node (ref "R515") (pin "2") (pinfunction "2_2") (pintype "passive"))
      (node (ref "VT505") (pin "1") (pinfunction "B_1") (pintype "passive"))
      (node (ref "VT506") (pin "1") (pinfunction "B_1") (pintype "passive"))
      (node (ref "VT506") (pin "2") (pinfunction "C_2") (pintype "passive"))
      (node (ref "VT506") (pin "4") (pinfunction "C_4") (pintype "passive"))
    )
    (net (code "65") (name "Net-(VT505-E)") (class "Default")
      (node (ref "R513") (pin "1") (pinfunction "1_1") (pintype "passive"))
      (node (ref "VT505") (pin "3") (pinfunction "E_3") (pintype "passive"))
    )
    (net (code "66") (name "Net-(VT506-E)") (class "Default")
      (node (ref "R514") (pin "1") (pinfunction "1_1") (pintype "passive"))
      (node (ref "VT506") (pin "3") (pinfunction "E_3") (pintype "passive"))
    )
    (net (code "67") (name "Net-(VT507-B)") (class "Default")
      (node (ref "R515") (pin "1") (pinfunction "1_1") (pintype "passive"))
      (node (ref "VT507") (pin "1") (pinfunction "B_1") (pintype "passive"))
      (node (ref "VT508") (pin "1") (pinfunction "B_1") (pintype "passive"))
      (node (ref "VT508") (pin "2") (pinfunction "C_2") (pintype "passive"))
      (node (ref "VT508") (pin "4") (pinfunction "C_4") (pintype "passive"))
    )
    (net (code "68") (name "Net-(VT507-E)") (class "Default")
      (node (ref "R516") (pin "2") (pinfunction "2_2") (pintype "passive"))
      (node (ref "VT507") (pin "3") (pinfunction "E_3") (pintype "passive"))
    )
    (net (code "69") (name "Net-(VT508-E)") (class "Default")
      (node (ref "R517") (pin "2") (pinfunction "2_2") (pintype "passive"))
      (node (ref "VT508") (pin "3") (pinfunction "E_3") (pintype "passive"))
    )
    (net (code "70") (name "Net-(VT509-G)") (class "Default")
      (node (ref "R532") (pin "2") (pinfunction "2_2") (pintype "passive"))
      (node (ref "R533") (pin "2") (pinfunction "2_2") (pintype "passive"))
      (node (ref "VT509") (pin "1") (pinfunction "G_1") (pintype "passive"))
    )
    (net (code "71") (name "U") (class "Default")
      (node (ref "C515") (pin "1") (pinfunction "1_1") (pintype "passive"))
      (node (ref "C516") (pin "1") (pinfunction "1_1") (pintype "passive"))
      (node (ref "DA502") (pin "6") (pinfunction "OUT_6") (pintype "passive"))
      (node (ref "KT502") (pin "1") (pinfunction "1_1") (pintype "passive"))
      (node (ref "R521") (pin "2") (pinfunction "2_2") (pintype "passive"))
      (node (ref "R522") (pin "2") (pinfunction "2_2") (pintype "passive"))
      (node (ref "R523") (pin "2") (pinfunction "2_2") (pintype "passive"))
    )
    (net (code "72") (name "UOC") (class "Default")
      (node (ref "C512") (pin "2") (pinfunction "2_2") (pintype "passive"))
      (node (ref "DA501") (pin "7") (pinfunction "OUT_7") (pintype "passive"))
      (node (ref "KT501") (pin "1") (pinfunction "1_1") (pintype "passive"))
      (node (ref "R504") (pin "2") (pinfunction "2_2") (pintype "passive"))
      (node (ref "R508") (pin "2") (pinfunction "2_2") (pintype "passive"))
      (node (ref "R511") (pin "1") (pinfunction "1_1") (pintype "passive"))
      (node (ref "R512") (pin "1") (pinfunction "1_1") (pintype "passive"))
      (node (ref "R518") (pin "1") (pinfunction "1_1") (pintype "passive"))
    )
    (net (code "73") (name "VS1+") (class "Default")
      (node (ref "DA506") (pin "5") (pinfunction "+U_5") (pintype "passive"))
      (node (ref "R535") (pin "1") (pinfunction "1_1") (pintype "passive"))
      (node (ref "VT503") (pin "3") (pinfunction "E_3") (pintype "passive"))
    )
    (net (code "74") (name "VS1-") (class "Default")
      (node (ref "DA506") (pin "2") (pinfunction "-U_2") (pintype "passive"))
      (node (ref "R536") (pin "1") (pinfunction "1_1") (pintype "passive"))
      (node (ref "VT504") (pin "3") (pinfunction "E_3") (pintype "passive"))
    )
    (net (code "75") (name "unconnected-(DA502-N-Pad1)") (class "Default")
      (node (ref "DA502") (pin "1") (pinfunction "N_1") (pintype "passive"))
    )
    (net (code "76") (name "unconnected-(DA502-N-Pad5)") (class "Default")
      (node (ref "DA502") (pin "5") (pinfunction "N_5") (pintype "passive"))
    )
    (net (code "77") (name "unconnected-(DA504-N-Pad1)") (class "Default")
      (node (ref "DA504") (pin "1") (pinfunction "N_1") (pintype "passive"))
    )
    (net (code "78") (name "unconnected-(DA504-N-Pad5)") (class "Default")
      (node (ref "DA504") (pin "5") (pinfunction "N_5") (pintype "passive"))
    )
  )
)
